# 1-1.net
KiCad netlist of a schematic drawn in EAGLE
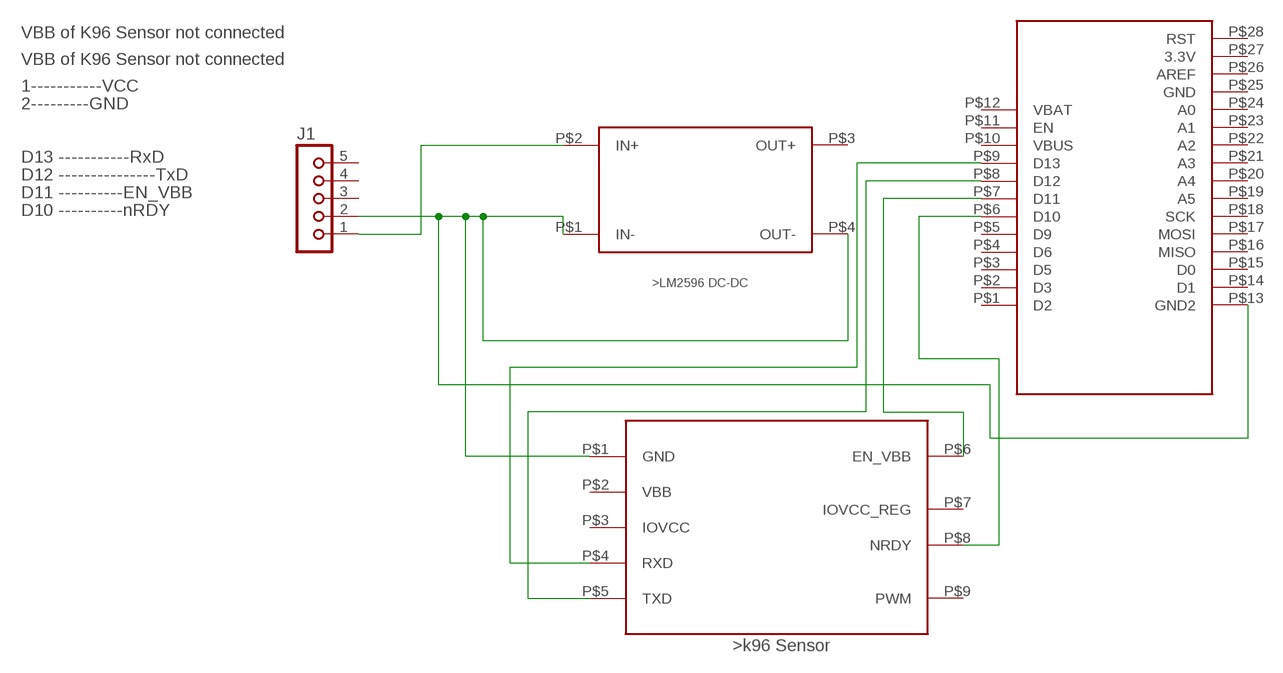
[diagram p0: schematic, sheet 1]

(export (version "E")
  (design (tool "Eeschema 10.0.6"))
  (components
    (comp (ref "DCDC1")
      (value "DCDC")
      (footprint "eagle-import:DCDC")
      (libsource (lib "eagle-import") (part "DCDC"))
    )
    (comp (ref "FEATHER1")
      (value "FEATHER")
      (footprint "eagle-import:FEATHER")
      (libsource (lib "eagle-import") (part "FEATHER"))
    )
    (comp (ref "J1")
      (value "JU05")
      (footprint "eagle-import:JU05")
      (libsource (lib "eagle-import") (part "JU05"))
    )
    (comp (ref "K96SENSOR1")
      (value "K96SENSOR")
      (footprint "eagle-import:K96SENSOR")
      (libsource (lib "eagle-import") (part "K96SENSOR"))
    )
  )
  (nets
    (net (code "1") (name "Net-(DCDC1-IN+)") (class "Default")
      (node (ref "DCDC1") (pin "P$2") (pinfunction "IN+_P$2") (pintype "bidirectional"))
      (node (ref "J1") (pin "1") (pinfunction "1_1") (pintype "passive"))
    )
    (net (code "2") (name "Net-(DCDC1-IN-)") (class "Default")
      (node (ref "DCDC1") (pin "P$1") (pinfunction "IN-_P$1") (pintype "bidirectional"))
      (node (ref "DCDC1") (pin "P$4") (pinfunction "OUT-_P$4") (pintype "bidirectional"))
      (node (ref "FEATHER1") (pin "P$13") (pinfunction "GND2_P$13") (pintype "bidirectional"))
      (node (ref "J1") (pin "2") (pinfunction "2_2") (pintype "passive"))
      (node (ref "K96SENSOR1") (pin "P$1") (pinfunction "GND_P$1") (pintype "bidirectional"))
    )
    (net (code "3") (name "Net-(FEATHER1-D10)") (class "Default")
      (node (ref "FEATHER1") (pin "P$6") (pinfunction "D10_P$6") (pintype "bidirectional"))
      (node (ref "K96SENSOR1") (pin "P$8") (pinfunction "NRDY_P$8") (pintype "bidirectional"))
    )
    (net (code "4") (name "Net-(FEATHER1-D11)") (class "Default")
      (node (ref "FEATHER1") (pin "P$7") (pinfunction "D11_P$7") (pintype "bidirectional"))
      (node (ref "K96SENSOR1") (pin "P$6") (pinfunction "EN_VBB_P$6") (pintype "bidirectional"))
    )
    (net (code "5") (name "Net-(FEATHER1-D12)") (class "Default")
      (node (ref "FEATHER1") (pin "P$8") (pinfunction "D12_P$8") (pintype "bidirectional"))
      (node (ref "K96SENSOR1") (pin "P$5") (pinfunction "TXD_P$5") (pintype "bidirectional"))
    )
    (net (code "6") (name "Net-(FEATHER1-D13)") (class "Default")
      (node (ref "FEATHER1") (pin "P$9") (pinfunction "D13_P$9") (pintype "bidirectional"))
      (node (ref "K96SENSOR1") (pin "P$4") (pinfunction "RXD_P$4") (pintype "bidirectional"))
    )
    (net (code "7") (name "unconnected-(DCDC1-OUT+-PadP$3)") (class "Default")
      (node (ref "DCDC1") (pin "P$3") (pinfunction "OUT+_P$3") (pintype "bidirectional"))
    )
    (net (code "8") (name "unconnected-(FEATHER1-3.3V-PadP$27)") (class "Default")
      (node (ref "FEATHER1") (pin "P$27") (pinfunction "3.3V_P$27") (pintype "bidirectional"))
    )
    (net (code "9") (name "unconnected-(FEATHER1-A0-PadP$24)") (class "Default")
      (node (ref "FEATHER1") (pin "P$24") (pinfunction "A0_P$24") (pintype "bidirectional"))
    )
    (net (code "10") (name "unconnected-(FEATHER1-A1-PadP$23)") (class "Default")
      (node (ref "FEATHER1") (pin "P$23") (pinfunction "A1_P$23") (pintype "bidirectional"))
    )
    (net (code "11") (name "unconnected-(FEATHER1-A2-PadP$22)") (class "Default")
      (node (ref "FEATHER1") (pin "P$22") (pinfunction "A2_P$22") (pintype "bidirectional"))
    )
    (net (code "12") (name "unconnected-(FEATHER1-A3-PadP$21)") (class "Default")
      (node (ref "FEATHER1") (pin "P$21") (pinfunction "A3_P$21") (pintype "bidirectional"))
    )
    (net (code "13") (name "unconnected-(FEATHER1-A4-PadP$20)") (class "Default")
      (node (ref "FEATHER1") (pin "P$20") (pinfunction "A4_P$20") (pintype "bidirectional"))
    )
    (net (code "14") (name "unconnected-(FEATHER1-A5-PadP$19)") (class "Default")
      (node (ref "FEATHER1") (pin "P$19") (pinfunction "A5_P$19") (pintype "bidirectional"))
    )
    (net (code "15") (name "unconnected-(FEATHER1-AREF-PadP$26)") (class "Default")
      (node (ref "FEATHER1") (pin "P$26") (pinfunction "AREF_P$26") (pintype "bidirectional"))
    )
    (net (code "16") (name "unconnected-(FEATHER1-D0-PadP$15)") (class "Default")
      (node (ref "FEATHER1") (pin "P$15") (pinfunction "D0_P$15") (pintype "bidirectional"))
    )
    (net (code "17") (name "unconnected-(FEATHER1-D1-PadP$14)") (class "Default")
      (node (ref "FEATHER1") (pin "P$14") (pinfunction "D1_P$14") (pintype "bidirectional"))
    )
    (net (code "18") (name "unconnected-(FEATHER1-D2-PadP$1)") (class "Default")
      (node (ref "FEATHER1") (pin "P$1") (pinfunction "D2_P$1") (pintype "bidirectional"))
    )
    (net (code "19") (name "unconnected-(FEATHER1-D3-PadP$2)") (class "Default")
      (node (ref "FEATHER1") (pin "P$2") (pinfunction "D3_P$2") (pintype "bidirectional"))
    )
    (net (code "20") (name "unconnected-(FEATHER1-D5-PadP$3)") (class "Default")
      (node (ref "FEATHER1") (pin "P$3") (pinfunction "D5_P$3") (pintype "bidirectional"))
    )
    (net (code "21") (name "unconnected-(FEATHER1-D6-PadP$4)") (class "Default")
      (node (ref "FEATHER1") (pin "P$4") (pinfunction "D6_P$4") (pintype "bidirectional"))
    )
    (net (code "22") (name "unconnected-(FEATHER1-D9-PadP$5)") (class "Default")
      (node (ref "FEATHER1") (pin "P$5") (pinfunction "D9_P$5") (pintype "bidirectional"))
    )
    (net (code "23") (name "unconnected-(FEATHER1-EN-PadP$11)") (class "Default")
      (node (ref "FEATHER1") (pin "P$11") (pinfunction "EN_P$11") (pintype "bidirectional"))
    )
    (net (code "24") (name "unconnected-(FEATHER1-GND-PadP$25)") (class "Default")
      (node (ref "FEATHER1") (pin "P$25") (pinfunction "GND_P$25") (pintype "bidirectional"))
    )
    (net (code "25") (name "unconnected-(FEATHER1-MISO-PadP$16)") (class "Default")
      (node (ref "FEATHER1") (pin "P$16") (pinfunction "MISO_P$16") (pintype "bidirectional"))
    )
    (net (code "26") (name "unconnected-(FEATHER1-MOSI-PadP$17)") (class "Default")
      (node (ref "FEATHER1") (pin "P$17") (pinfunction "MOSI_P$17") (pintype "bidirectional"))
    )
    (net (code "27") (name "unconnected-(FEATHER1-RST-PadP$28)") (class "Default")
      (node (ref "FEATHER1") (pin "P$28") (pinfunction "RST_P$28") (pintype "bidirectional"))
    )
    (net (code "28") (name "unconnected-(FEATHER1-SCK-PadP$18)") (class "Default")
      (node (ref "FEATHER1") (pin "P$18") (pinfunction "SCK_P$18") (pintype "bidirectional"))
    )
    (net (code "29") (name "unconnected-(FEATHER1-VBAT-PadP$12)") (class "Default")
      (node (ref "FEATHER1") (pin "P$12") (pinfunction "VBAT_P$12") (pintype "bidirectional"))
    )
    (net (code "30") (name "unconnected-(FEATHER1-VBUS-PadP$10)") (class "Default")
      (node (ref "FEATHER1") (pin "P$10") (pinfunction "VBUS_P$10") (pintype "bidirectional"))
    )
    (net (code "31") (name "unconnected-(J1-Pad3)") (class "Default")
      (node (ref "J1") (pin "3") (pinfunction "3_3") (pintype "passive"))
    )
    (net (code "32") (name "unconnected-(J1-Pad4)") (class "Default")
      (node (ref "J1") (pin "4") (pinfunction "4_4") (pintype "passive"))
    )
    (net (code "33") (name "unconnected-(J1-Pad5)") (class "Default")
      (node (ref "J1") (pin "5") (pinfunction "5_5") (pintype "passive"))
    )
    (net (code "34") (name "unconnected-(K96SENSOR1-IOVCC-PadP$3)") (class "Default")
      (node (ref "K96SENSOR1") (pin "P$3") (pinfunction "IOVCC_P$3") (pintype "bidirectional"))
    )
    (net (code "35") (name "unconnected-(K96SENSOR1-IOVCC_REG-PadP$7)") (class "Default")
      (node (ref "K96SENSOR1") (pin "P$7") (pinfunction "IOVCC_REG_P$7") (pintype "bidirectional"))
    )
    (net (code "36") (name "unconnected-(K96SENSOR1-PWM-PadP$9)") (class "Default")
      (node (ref "K96SENSOR1") (pin "P$9") (pinfunction "PWM_P$9") (pintype "bidirectional"))
    )
    (net (code "37") (name "unconnected-(K96SENSOR1-VBB-PadP$2)") (class "Default")
      (node (ref "K96SENSOR1") (pin "P$2") (pinfunction "VBB_P$2") (pintype "bidirectional"))
    )
  )
)
